# improved_serial_interface.net
KiCad netlist of a schematic drawn in EAGLE
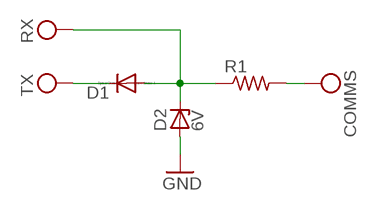
[diagram p0: schematic, sheet 1]

(export (version "E")
  (design (tool "Eeschema 10.0.6"))
  (components
    (comp (ref "D1")
      (value "1N4148DO35-10")
      (footprint "eagle-import:DO35-10")
      (libsource (lib "eagle-import") (part "1N4148DO35-10"))
    )
    (comp (ref "D2")
      (value "6V")
      (footprint "eagle-import:DO34Z7")
      (libsource (lib "eagle-import") (part "BZV10"))
    )
    (comp (ref "R1")
      (value "R-US_0207/10")
      (footprint "eagle-import:0207_10")
      (libsource (lib "eagle-import") (part "R-US_0207/10"))
    )
  )
  (nets
    (net (code "1") (name "COMMS") (class "Default")
      (node (ref "D1") (pin "A") (pinfunction "A_A") (pintype "passive"))
      (node (ref "D1") (pin "C") (pinfunction "C_C") (pintype "passive"))
      (node (ref "D2") (pin "C") (pinfunction "C_C") (pintype "passive"))
      (node (ref "R1") (pin "1") (pinfunction "1_1") (pintype "passive"))
      (node (ref "R1") (pin "2") (pinfunction "2_2") (pintype "passive"))
    )
    (net (code "2") (name "GND") (class "Default")
      (node (ref "D2") (pin "A") (pinfunction "A_A") (pintype "passive"))
    )
  )
)
